# EvoProject_2_0.net
KiCad netlist of a schematic drawn in Altium Designer
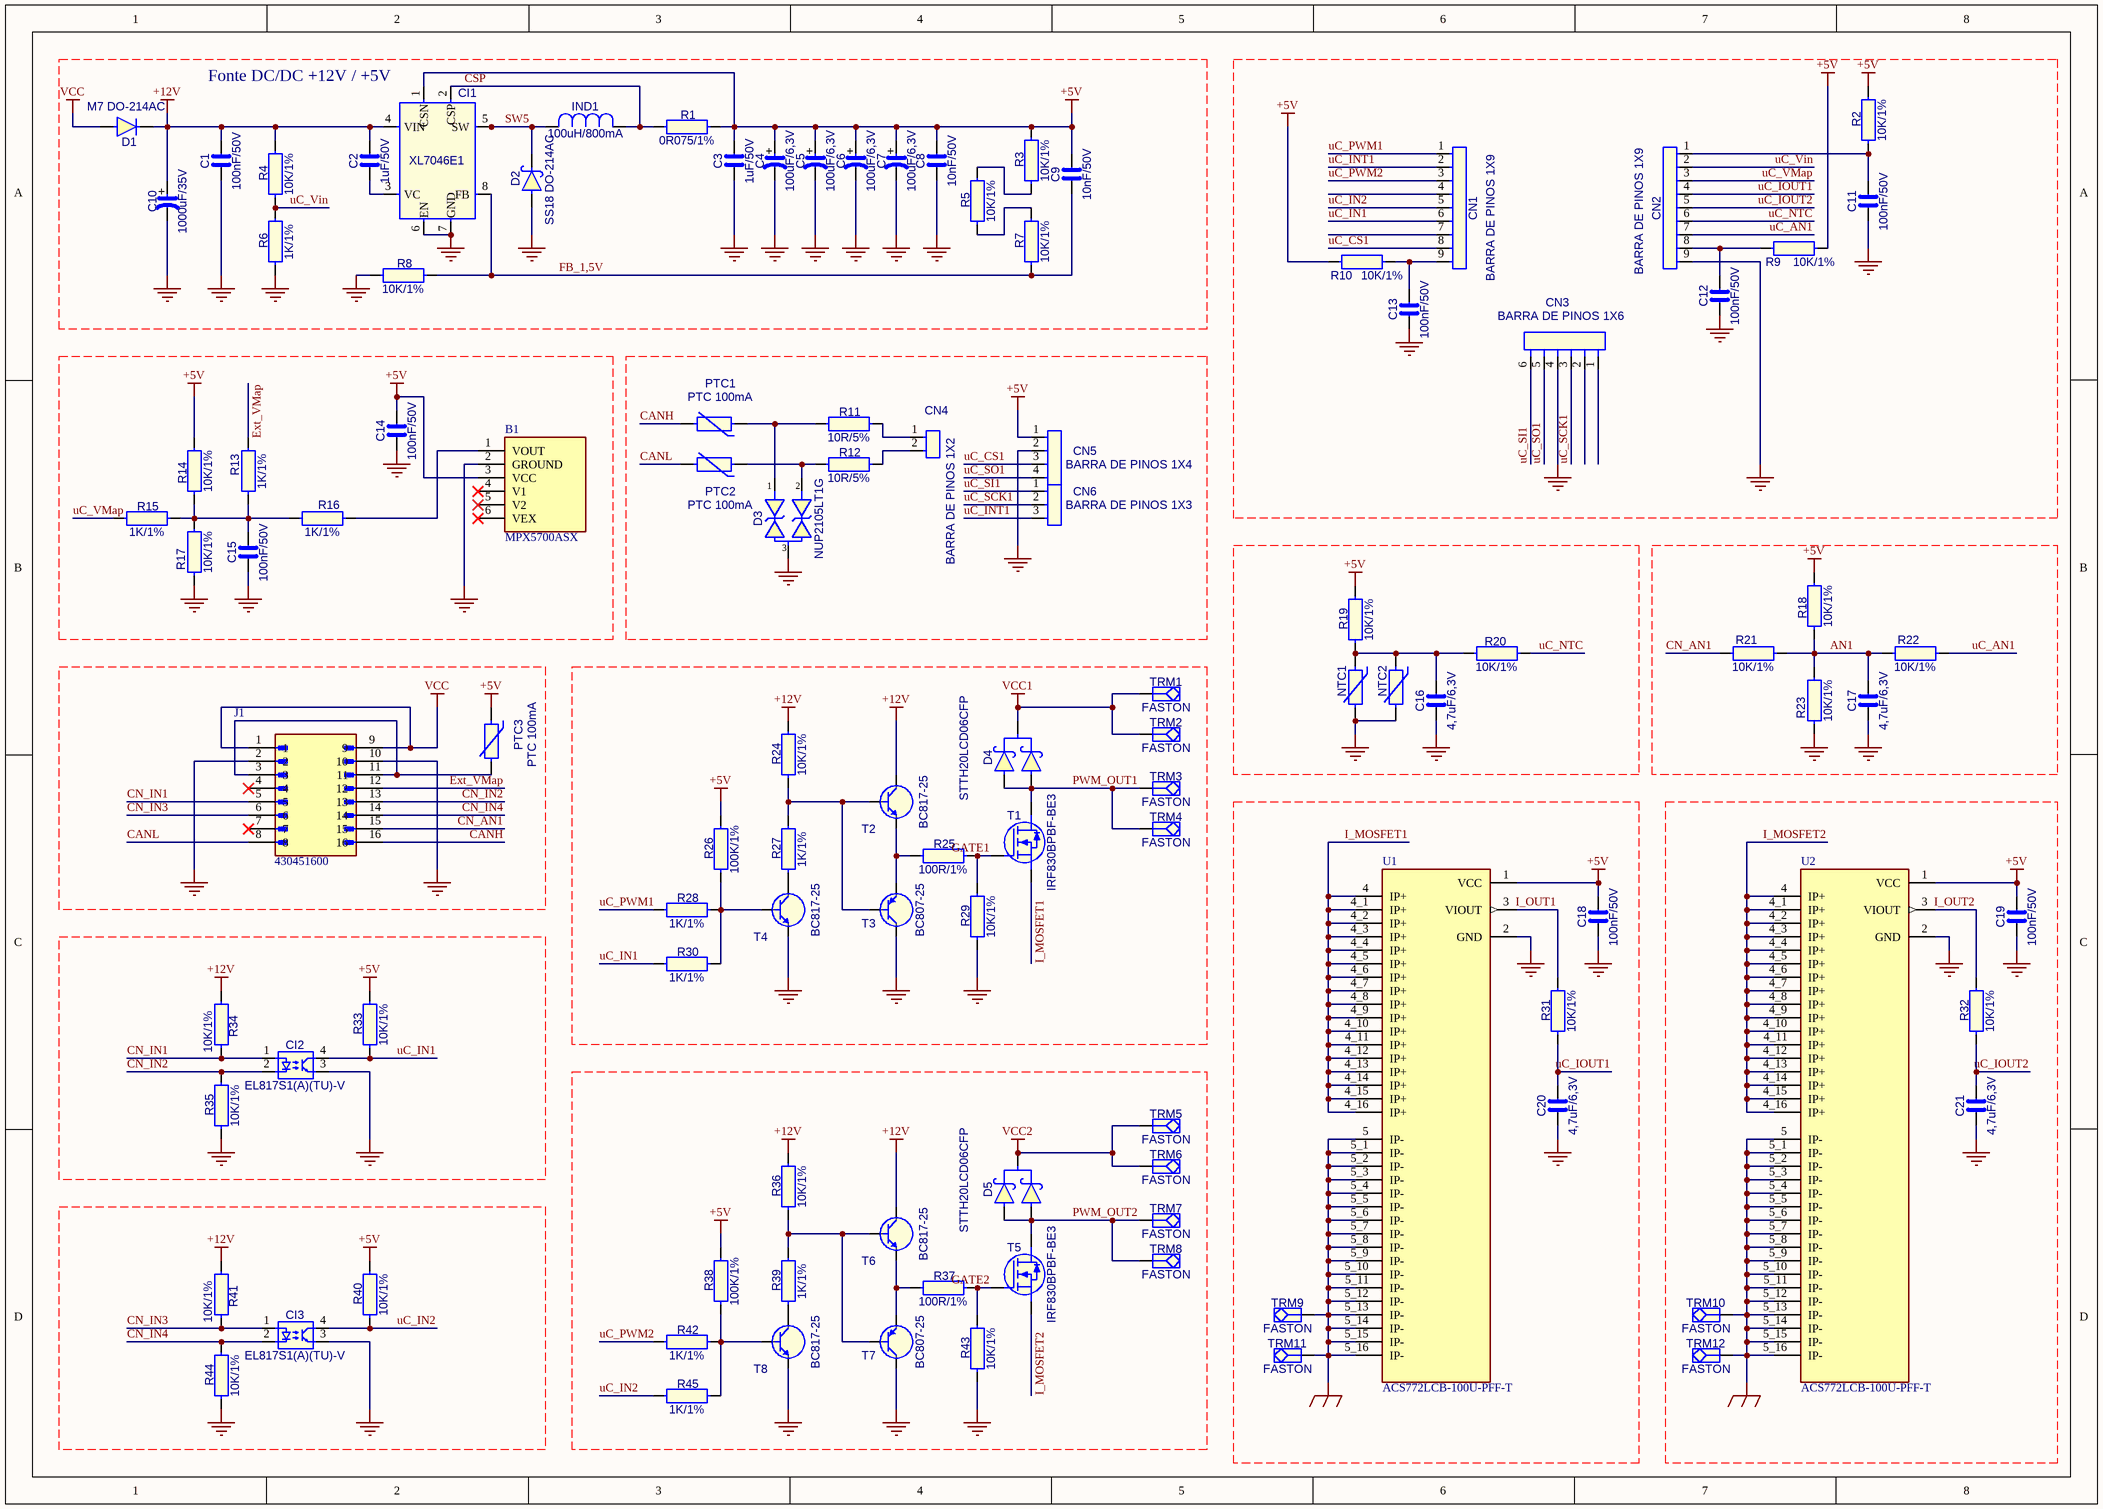
[diagram p0: EvoProject 2.0.SchDoc]

(export (version "E")
  (design (tool "Eeschema 10.0.6"))
  (components
    (comp (ref "B1")
      (value "MPX5700ASX")
      (footprint "MPX5700ASX")
      (libsource (lib "Inova_2015") (part "MPX5700ASX"))
    )
    (comp (ref "C1")
      (value "100nF/50V")
      (footprint "CAP SMD CE 0603 HR")
      (description "CAPACITOR SMD CE 0603 100nF 50V 10% X7R")
      (libsource (lib "INOVA SISTEMAS ELETRONICOS") (part "CAP_NP"))
    )
    (comp (ref "C2")
      (value "1uF/50V")
      (footprint "CAP SMD CE 0603 HR")
      (description "CAPACITOR SMD CE 0603 1uF 50V 10% X5R")
      (libsource (lib "INOVA SISTEMAS ELETRONICOS") (part "CAP_NP"))
    )
    (comp (ref "C3")
      (value "1uF/50V")
      (footprint "CAP SMD CE 0603 HR")
      (description "CAPACITOR SMD CE 0603 1uF 50V 10% X5R")
      (libsource (lib "INOVA SISTEMAS ELETRONICOS") (part "CAP_NP"))
    )
    (comp (ref "C4")
      (value "100uF/6,3V")
      (footprint "CAP SMD EL D.6,30 H.5,40 P.4,80 HR")
      (description "CAPACITOR SMD EL D.6.3 H.5.4mm 100uF 6.3V 20% BESR")
      (libsource (lib "INOVA SISTEMAS ELETRONICOS") (part "CAP_P"))
    )
    (comp (ref "C5")
      (value "100uF/6,3V")
      (footprint "CAP SMD EL D.6,30 H.5,40 P.4,80 HR")
      (description "CAPACITOR SMD EL D.6.3 H.5.4mm 100uF 6.3V 20% BESR")
      (libsource (lib "INOVA SISTEMAS ELETRONICOS") (part "CAP_P"))
    )
    (comp (ref "C6")
      (value "100uF/6,3V")
      (footprint "CAP SMD EL D.6,30 H.5,40 P.4,80 HR")
      (description "CAPACITOR SMD EL D.6.3 H.5.4mm 100uF 6.3V 20% BESR")
      (libsource (lib "INOVA SISTEMAS ELETRONICOS") (part "CAP_P"))
    )
    (comp (ref "C7")
      (value "100uF/6,3V")
      (footprint "CAP SMD EL D.6,30 H.5,40 P.4,80 HR")
      (description "CAPACITOR SMD EL D.6.3 H.5.4mm 100uF 6.3V 20% BESR")
      (libsource (lib "INOVA SISTEMAS ELETRONICOS") (part "CAP_P"))
    )
    (comp (ref "C8")
      (value "10nF/50V")
      (footprint "CAP SMD CE 0603 HR")
      (description "CAPACITOR SMD CE 0603 10nF 50V 20% X7R")
      (libsource (lib "INOVA SISTEMAS ELETRONICOS") (part "CAP_NP"))
    )
    (comp (ref "C9")
      (value "10nF/50V")
      (footprint "CAP SMD CE 0603 HR")
      (description "CAPACITOR SMD CE 0603 10nF 50V 20% X7R")
      (libsource (lib "INOVA SISTEMAS ELETRONICOS") (part "CAP_NP"))
    )
    (comp (ref "C10")
      (value "1000uF/35V")
      (footprint "CAP PTH EL D.13,00 H.20,00 P.5,00 RD MW")
      (description "CAPACITOR PTH EL 1000/35 20%")
      (libsource (lib "INOVA SISTEMAS ELETRONICOS") (part "CAP_P"))
    )
    (comp (ref "C11")
      (value "100nF/50V")
      (footprint "CAP SMD CE 0603 HR")
      (description "CAPACITOR SMD CE 0603 100nF 50V 10% X7R")
      (libsource (lib "INOVA SISTEMAS ELETRONICOS") (part "CAP_NP"))
    )
    (comp (ref "C12")
      (value "100nF/50V")
      (footprint "CAP SMD CE 0603 HR")
      (description "CAPACITOR SMD CE 0603 100nF 50V 10% X7R")
      (libsource (lib "INOVA SISTEMAS ELETRONICOS") (part "CAP_NP"))
    )
    (comp (ref "C13")
      (value "100nF/50V")
      (footprint "CAP SMD CE 0603 HR")
      (description "CAPACITOR SMD CE 0603 100nF 50V 10% X7R")
      (libsource (lib "INOVA SISTEMAS ELETRONICOS") (part "CAP_NP"))
    )
    (comp (ref "C14")
      (value "100nF/50V")
      (footprint "CAP SMD CE 0603 HR")
      (description "CAPACITOR SMD CE 0603 100nF 50V 10% X7R")
      (libsource (lib "INOVA SISTEMAS ELETRONICOS") (part "CAP_NP"))
    )
    (comp (ref "C15")
      (value "100nF/50V")
      (footprint "CAP SMD CE 0603 HR")
      (description "CAPACITOR SMD CE 0603 100nF 50V 10% X7R")
      (libsource (lib "INOVA SISTEMAS ELETRONICOS") (part "CAP_NP"))
    )
    (comp (ref "C16")
      (value "4,7uF/6,3V")
      (footprint "CAP SMD CE 0603 HR")
      (description "CAPACITOR SMD CE 0603 4,7uF 6.3V 10% X5R")
      (libsource (lib "INOVA SISTEMAS ELETRONICOS") (part "CAP_NP"))
    )
    (comp (ref "C17")
      (value "4,7uF/6,3V")
      (footprint "CAP SMD CE 0603 HR")
      (description "CAPACITOR SMD CE 0603 4,7uF 6.3V 10% X5R")
      (libsource (lib "INOVA SISTEMAS ELETRONICOS") (part "CAP_NP"))
    )
    (comp (ref "C18")
      (value "100nF/50V")
      (footprint "CAP SMD CE 0603 HR")
      (description "CAPACITOR SMD CE 0603 100nF 50V 10% X7R")
      (libsource (lib "INOVA SISTEMAS ELETRONICOS") (part "CAP_NP"))
    )
    (comp (ref "C19")
      (value "100nF/50V")
      (footprint "CAP SMD CE 0603 HR")
      (description "CAPACITOR SMD CE 0603 100nF 50V 10% X7R")
      (libsource (lib "INOVA SISTEMAS ELETRONICOS") (part "CAP_NP"))
    )
    (comp (ref "C20")
      (value "4,7uF/6,3V")
      (footprint "CAP SMD CE 0603 HR")
      (description "CAPACITOR SMD CE 0603 4,7uF 6.3V 10% X5R")
      (libsource (lib "INOVA SISTEMAS ELETRONICOS") (part "CAP_NP"))
    )
    (comp (ref "C21")
      (value "4,7uF/6,3V")
      (footprint "CAP SMD CE 0603 HR")
      (description "CAPACITOR SMD CE 0603 4,7uF 6.3V 10% X5R")
      (libsource (lib "INOVA SISTEMAS ELETRONICOS") (part "CAP_NP"))
    )
    (comp (ref "CI1")
      (value "XL7046E1")
      (footprint "GEN SMD SOIC8 TP P.1,27 MR")
      (description "CI SMD REBAIXADOR DE TENSÃO XL7046E1")
      (libsource (lib "INOVA SISTEMAS ELETRONICOS") (part "CI_XL7046"))
    )
    (comp (ref "CI2")
      (value "EL817S1(A)(TU)-V")
      (footprint "GEN SMD SOIC4 P.1,27 MR")
      (description "CI OPTOACOPLADOR SMD DIP-4 1CH 817 70V 80~160%")
      (libsource (lib "INOVA SISTEMAS ELETRONICOS") (part "OPT_4 pinos"))
    )
    (comp (ref "CI3")
      (value "EL817S1(A)(TU)-V")
      (footprint "GEN SMD SOIC4 P.1,27 MR")
      (description "CI OPTOACOPLADOR SMD DIP-4 1CH 817 70V 80~160%")
      (libsource (lib "INOVA SISTEMAS ELETRONICOS") (part "OPT_4 pinos"))
    )
    (comp (ref "CN1")
      (value "BARRA DE PINOS 1X9")
      (footprint "CON PTH BAR P.2,54 1x9 180D MW")
      (description "BARRA DE PINOS 180° RETOS (CORTAR 9 PINOS)")
      (libsource (lib "INOVA SISTEMAS ELETRONICOS") (part "CON_9 Vias Simples"))
    )
    (comp (ref "CN2")
      (value "BARRA DE PINOS 1X9")
      (footprint "CON PTH BAR P.2,54 1x9 180D MW")
      (description "BARRA DE PINOS 180° RETOS (CORTAR 9 PINOS)")
      (libsource (lib "") (part "CON_9 Vias Simples_1"))
    )
    (comp (ref "CN3")
      (value "BARRA DE PINOS 1X6")
      (footprint "CON PTH BAR  W. L. H. P.2,54mm 1x6 180D MW")
      (description "CONECTOR BARRA DE PINOS 180° 1X6")
      (libsource (lib "INOVA SISTEMAS ELETRONICOS") (part "CON_6 Vias Simples"))
    )
    (comp (ref "CN4")
      (value "BARRA DE PINOS 1X2")
      (footprint "CON PTH BAR  W. L. H. P.02,54mm 1x2 180D MW")
      (description "BARRA DE PINOS 180° RETOS (CORTAR 2 PINOS)")
      (libsource (lib "INOVA SISTEMAS ELETRONICOS") (part "CON_2 Vias Simples"))
    )
    (comp (ref "CN5")
      (value "BARRA DE PINOS 1X4")
      (footprint "CON PTH BAR  W. L. H. P.02,54mm 1x4 180D MW")
      (description "BARRA DE PINOS 180° RETOS (CORTAR 4 PINOS)")
      (libsource (lib "INOVA SISTEMAS ELETRONICOS") (part "CON_4 Vias Simples"))
    )
    (comp (ref "CN6")
      (value "BARRA DE PINOS 1X3")
      (footprint "CON PTH BAR  W. L. H. P.2,54mm 1x3 180D MW")
      (description "BARRA DE PINOS 180° RETOS (CORTAR 3 PINOS)")
      (libsource (lib "INOVA SISTEMAS ELETRONICOS") (part "CON_3 Vias Simples"))
    )
    (comp (ref "D1")
      (value "M7 DO-214AC")
      (footprint "DIO SMD SMA DO214AC MR")
      (description "DIODO SMD 1N4007 SMA")
      (libsource (lib "INOVA SISTEMAS ELETRONICOS") (part "DIO_Comum"))
    )
    (comp (ref "D2")
      (value "SS18 DO-214AC")
      (footprint "DIO SMD SMA DO214AC HR")
      (description "DIODO SMD SS18 1A 80V SCHOTTKY")
      (libsource (lib "INOVA SISTEMAS ELETRONICOS") (part "DIO_Schottky"))
    )
    (comp (ref "D3")
      (value "NUP2105LT1G")
      (footprint "GEN SMD SOT23-3 TO-236AA MR")
      (description "DIODO SMD TVS SOT23 24V 50A 350W")
      (libsource (lib "INOVA SISTEMAS ELETRONICOS") (part "DIO_NUP2105L"))
    )
    (comp (ref "D4")
      (value "STTH20LCD06CFP")
      (footprint "GEN PTH TO-220AB P.2,54 LW")
      (description "DIODO PTH STTH20LCD06CFP ULTRAFAST (PF07-6.5-V)")
      (libsource (lib "INOVA SISTEMAS ELETRONICOS") (part "DIO_Schottky Duplo"))
    )
    (comp (ref "D5")
      (value "STTH20LCD06CFP")
      (footprint "GEN PTH TO-220AB P.2,54 LW")
      (description "DIODO PTH STTH20LCD06CFP ULTRAFAST (PF07-6.5-V)")
      (libsource (lib "INOVA SISTEMAS ELETRONICOS") (part "DIO_Schottky Duplo"))
    )
    (comp (ref "IND1")
      (value "100uH/800mA")
      (footprint "IND SMD L.6,30 P.4,82 MR")
      (description "INDUTOR SMD 100uH 800mA")
      (libsource (lib "INOVA SISTEMAS ELETRONICOS") (part "IND_2 Terminais"))
    )
    (comp (ref "J1")
      (value "430451600")
      (footprint "MOLEX_430451600")
      (description "Conn Wire to Board HDR 16 POS 3mm Solder RA Side Entry Thru-Hole Micro-Fit 3.0â„¢ Tray")
      (fields (field (name "MF") "Molex"))
      (libsource (lib "430451600") (part "430451600"))
    )
    (comp (ref "NTC1")
      (value "MF52A103H3950(A2)")
      (footprint "RES PTH NTC RADIAL P.2,54 LW")
      (description "TERMISTOR NTC 10K (PF)")
      (libsource (lib "INOVA SISTEMAS ELETRONICOS") (part "RES_NTC"))
    )
    (comp (ref "NTC2")
      (value "NTC 10k")
      (footprint "RES SMD CH 0805 HR")
      (description "TERMISTOR SMD NTC 0805 10K BETA 3970 3%")
      (libsource (lib "INOVA SISTEMAS ELETRONICOS") (part "RES_NTC"))
    )
    (comp (ref "PTC1")
      (value "PTC 100mA")
      (footprint "PTC SMD CH 0805 HR")
      (description "TERMISTOR SMD PTC 0805 0,1A 24V NHC")
      (libsource (lib "INOVA SISTEMAS ELETRONICOS") (part "RES_PTC"))
    )
    (comp (ref "PTC2")
      (value "PTC 100mA")
      (footprint "PTC SMD CH 0805 HR")
      (description "TERMISTOR SMD PTC 0805 0,1A 24V NHC")
      (libsource (lib "INOVA SISTEMAS ELETRONICOS") (part "RES_PTC"))
    )
    (comp (ref "PTC3")
      (value "PTC 100mA")
      (footprint "PTC SMD CH 0805 HR")
      (description "TERMISTOR SMD PTC 0805 0,1A 24V NHC")
      (libsource (lib "") (part "RES_PTC_1"))
    )
    (comp (ref "R1")
      (value "0R075/1%")
      (footprint "RES SMD CH 1206 HR")
      (description "RESISTOR SMD CH 1206 0R075 1% 1/4W")
      (libsource (lib "") (part "RES_Geral_1"))
    )
    (comp (ref "R2")
      (value "10K/1%")
      (footprint "RES SMD CH 0603 HR")
      (description "RESISTOR SMD CH 0603 10K 1% 1/10W")
      (libsource (lib "INOVA SISTEMAS ELETRONICOS") (part "RES_Geral"))
    )
    (comp (ref "R3")
      (value "10K/1%")
      (footprint "RES SMD CH 0603 HR")
      (description "RESISTOR SMD CH 0603 10K 1% 1/10W")
      (libsource (lib "INOVA SISTEMAS ELETRONICOS") (part "RES_Geral"))
    )
    (comp (ref "R4")
      (value "10K/1%")
      (footprint "RES SMD CH 0603 HR")
      (description "RESISTOR SMD CH 0603 10K 1% 1/10W")
      (libsource (lib "INOVA SISTEMAS ELETRONICOS") (part "RES_Geral"))
    )
    (comp (ref "R5")
      (value "10K/1%")
      (footprint "RES SMD CH 0603 HR")
      (description "RESISTOR SMD CH 0603 10K 1% 1/10W")
      (libsource (lib "INOVA SISTEMAS ELETRONICOS") (part "RES_Geral"))
    )
    (comp (ref "R6")
      (value "1K/1%")
      (footprint "RES SMD CH 0603 HR")
      (description "RESISTOR SMD CH 0603 1K 1% 1/10W")
      (libsource (lib "INOVA SISTEMAS ELETRONICOS") (part "RES_Geral"))
    )
    (comp (ref "R7")
      (value "10K/1%")
      (footprint "RES SMD CH 0603 HR")
      (description "RESISTOR SMD CH 0603 10K 1% 1/10W")
      (libsource (lib "INOVA SISTEMAS ELETRONICOS") (part "RES_Geral"))
    )
    (comp (ref "R8")
      (value "10K/1%")
      (footprint "RES SMD CH 0603 HR")
      (description "RESISTOR SMD CH 0603 10K 1% 1/10W")
      (libsource (lib "") (part "RES_Geral_1"))
    )
    (comp (ref "R9")
      (value "10K/1%")
      (footprint "RES SMD CH 0603 HR")
      (description "RESISTOR SMD CH 0603 10K 1% 1/10W")
      (libsource (lib "") (part "RES_Geral_3"))
    )
    (comp (ref "R10")
      (value "10K/1%")
      (footprint "RES SMD CH 0603 HR")
      (description "RESISTOR SMD CH 0603 10K 1% 1/10W")
      (libsource (lib "") (part "RES_Geral_3"))
    )
    (comp (ref "R11")
      (value "10R/5%")
      (footprint "RES SMD CH 0603 HR")
      (description "RESISTOR SMD CH 0603 10R 5% 1/10W")
      (libsource (lib "") (part "RES_Geral_1"))
    )
    (comp (ref "R12")
      (value "10R/5%")
      (footprint "RES SMD CH 0603 HR")
      (description "RESISTOR SMD CH 0603 10R 5% 1/10W")
      (libsource (lib "") (part "RES_Geral_1"))
    )
    (comp (ref "R13")
      (value "1K/1%")
      (footprint "RES SMD CH 0603 HR")
      (description "RESISTOR SMD CH 0603 1K 1% 1/10W")
      (libsource (lib "INOVA SISTEMAS ELETRONICOS") (part "RES_Geral"))
    )
    (comp (ref "R14")
      (value "10K/1%")
      (footprint "RES SMD CH 0603 HR")
      (description "RESISTOR SMD CH 0603 10K 1% 1/10W")
      (libsource (lib "") (part "RES_Geral_2"))
    )
    (comp (ref "R15")
      (value "1K/1%")
      (footprint "RES SMD CH 0603 HR")
      (description "RESISTOR SMD CH 0603 1K 1% 1/10W")
      (libsource (lib "") (part "RES_Geral_1"))
    )
    (comp (ref "R16")
      (value "1K/1%")
      (footprint "RES SMD CH 0603 HR")
      (description "RESISTOR SMD CH 0603 1K 1% 1/10W")
      (libsource (lib "") (part "RES_Geral_1"))
    )
    (comp (ref "R17")
      (value "10K/1%")
      (footprint "RES SMD CH 0603 HR")
      (description "RESISTOR SMD CH 0603 10K 1% 1/10W")
      (libsource (lib "") (part "RES_Geral_2"))
    )
    (comp (ref "R18")
      (value "10K/1%")
      (footprint "RES SMD CH 0603 HR")
      (description "RESISTOR SMD CH 0603 10K 1% 1/10W")
      (libsource (lib "") (part "RES_Geral_2"))
    )
    (comp (ref "R19")
      (value "10K/1%")
      (footprint "RES SMD CH 0603 HR")
      (description "RESISTOR SMD CH 0603 10K 1% 1/10W")
      (libsource (lib "INOVA SISTEMAS ELETRONICOS") (part "RES_Geral"))
    )
    (comp (ref "R20")
      (value "10K/1%")
      (footprint "RES SMD CH 0603 HR")
      (description "RESISTOR SMD CH 0603 10K 1% 1/10W")
      (libsource (lib "") (part "RES_Geral_3"))
    )
    (comp (ref "R21")
      (value "10K/1%")
      (footprint "RES SMD CH 0603 HR")
      (description "RESISTOR SMD CH 0603 10K 1% 1/10W")
      (libsource (lib "") (part "RES_Geral_3"))
    )
    (comp (ref "R22")
      (value "10K/1%")
      (footprint "RES SMD CH 0603 HR")
      (description "RESISTOR SMD CH 0603 10K 1% 1/10W")
      (libsource (lib "") (part "RES_Geral_3"))
    )
    (comp (ref "R23")
      (value "10K/1%")
      (footprint "RES SMD CH 0603 HR")
      (description "RESISTOR SMD CH 0603 10K 1% 1/10W")
      (libsource (lib "") (part "RES_Geral_2"))
    )
    (comp (ref "R24")
      (value "10K/1%")
      (footprint "RES SMD CH 0603 HR")
      (description "RESISTOR SMD CH 0603 10K 1% 1/10W")
      (libsource (lib "INOVA SISTEMAS ELETRONICOS") (part "RES_Geral"))
    )
    (comp (ref "R25")
      (value "100R/1%")
      (footprint "RES SMD CH 0603 HR")
      (description "RESISTOR SMD CH 0603 100R 1% 1/10W")
      (libsource (lib "") (part "RES_Geral_1"))
    )
    (comp (ref "R26")
      (value "100K/1%")
      (footprint "RES SMD CH 0603 HR")
      (description "RESISTOR SMD CH 0603 100K 1% 1/10W")
      (libsource (lib "INOVA SISTEMAS ELETRONICOS") (part "RES_Geral"))
    )
    (comp (ref "R27")
      (value "1K/1%")
      (footprint "RES SMD CH 0603 HR")
      (description "RESISTOR SMD CH 0603 1K 1% 1/10W")
      (libsource (lib "INOVA SISTEMAS ELETRONICOS") (part "RES_Geral"))
    )
    (comp (ref "R28")
      (value "1K/1%")
      (footprint "RES SMD CH 0603 HR")
      (description "RESISTOR SMD CH 0603 1K 1% 1/10W")
      (libsource (lib "") (part "RES_Geral_1"))
    )
    (comp (ref "R29")
      (value "10K/1%")
      (footprint "RES SMD CH 0603 HR")
      (description "RESISTOR SMD CH 0603 10K 1% 1/10W")
      (libsource (lib "INOVA SISTEMAS ELETRONICOS") (part "RES_Geral"))
    )
    (comp (ref "R30")
      (value "1K/1%")
      (footprint "RES SMD CH 0603 HR")
      (description "RESISTOR SMD CH 0603 1K 1% 1/10W")
      (libsource (lib "") (part "RES_Geral_1"))
    )
    (comp (ref "R31")
      (value "10K/1%")
      (footprint "RES SMD CH 0603 HR")
      (description "RESISTOR SMD CH 0603 10K 1% 1/10W")
      (libsource (lib "INOVA SISTEMAS ELETRONICOS") (part "RES_Geral"))
    )
    (comp (ref "R32")
      (value "10K/1%")
      (footprint "RES SMD CH 0603 HR")
      (description "RESISTOR SMD CH 0603 10K 1% 1/10W")
      (libsource (lib "INOVA SISTEMAS ELETRONICOS") (part "RES_Geral"))
    )
    (comp (ref "R33")
      (value "10K/1%")
      (footprint "RES SMD CH 0603 HR")
      (description "RESISTOR SMD CH 0603 10K 1% 1/10W")
      (libsource (lib "INOVA SISTEMAS ELETRONICOS") (part "RES_Geral"))
    )
    (comp (ref "R34")
      (value "10K/1%")
      (footprint "RES SMD CH 0603 HR")
      (description "RESISTOR SMD CH 0603 10K 1% 1/10W")
      (libsource (lib "") (part "RES_Geral_3"))
    )
    (comp (ref "R35")
      (value "10K/1%")
      (footprint "RES SMD CH 0603 HR")
      (description "RESISTOR SMD CH 0603 10K 1% 1/10W")
      (libsource (lib "INOVA SISTEMAS ELETRONICOS") (part "RES_Geral"))
    )
    (comp (ref "R36")
      (value "10K/1%")
      (footprint "RES SMD CH 0603 HR")
      (description "RESISTOR SMD CH 0603 10K 1% 1/10W")
      (libsource (lib "INOVA SISTEMAS ELETRONICOS") (part "RES_Geral"))
    )
    (comp (ref "R37")
      (value "100R/1%")
      (footprint "RES SMD CH 0603 HR")
      (description "RESISTOR SMD CH 0603 100R 1% 1/10W")
      (libsource (lib "") (part "RES_Geral_1"))
    )
    (comp (ref "R38")
      (value "100K/1%")
      (footprint "RES SMD CH 0603 HR")
      (description "RESISTOR SMD CH 0603 100K 1% 1/10W")
      (libsource (lib "INOVA SISTEMAS ELETRONICOS") (part "RES_Geral"))
    )
    (comp (ref "R39")
      (value "1K/1%")
      (footprint "RES SMD CH 0603 HR")
      (description "RESISTOR SMD CH 0603 1K 1% 1/10W")
      (libsource (lib "INOVA SISTEMAS ELETRONICOS") (part "RES_Geral"))
    )
    (comp (ref "R40")
      (value "10K/1%")
      (footprint "RES SMD CH 0603 HR")
      (description "RESISTOR SMD CH 0603 10K 1% 1/10W")
      (libsource (lib "INOVA SISTEMAS ELETRONICOS") (part "RES_Geral"))
    )
    (comp (ref "R41")
      (value "10K/1%")
      (footprint "RES SMD CH 0603 HR")
      (description "RESISTOR SMD CH 0603 10K 1% 1/10W")
      (libsource (lib "") (part "RES_Geral_3"))
    )
    (comp (ref "R42")
      (value "1K/1%")
      (footprint "RES SMD CH 0603 HR")
      (description "RESISTOR SMD CH 0603 1K 1% 1/10W")
      (libsource (lib "") (part "RES_Geral_1"))
    )
    (comp (ref "R43")
      (value "10K/1%")
      (footprint "RES SMD CH 0603 HR")
      (description "RESISTOR SMD CH 0603 10K 1% 1/10W")
      (libsource (lib "INOVA SISTEMAS ELETRONICOS") (part "RES_Geral"))
    )
    (comp (ref "R44")
      (value "10K/1%")
      (footprint "RES SMD CH 0603 HR")
      (description "RESISTOR SMD CH 0603 10K 1% 1/10W")
      (libsource (lib "INOVA SISTEMAS ELETRONICOS") (part "RES_Geral"))
    )
    (comp (ref "R45")
      (value "1K/1%")
      (footprint "RES SMD CH 0603 HR")
      (description "RESISTOR SMD CH 0603 1K 1% 1/10W")
      (libsource (lib "") (part "RES_Geral_1"))
    )
    (comp (ref "T1")
      (value "IRF830BPBF-BE3")
      (footprint "GEN PTH TO-220AB P.2,54 LW")
      (description "TRANSISTOR PTH MOSFET IRF830BPBF-BE3 500V, 5,5A @ 25C°")
      (libsource (lib "INOVA SISTEMAS ELETRONICOS") (part "TRA_MOSFET_N-DPAK TO-252-3 TO-220AB"))
    )
    (comp (ref "T2")
      (value "BC817-25")
      (footprint "GEN SMD SOT23-3 TO-236AA MR")
      (description "TRANSISTOR SMD 817/25")
      (libsource (lib "INOVA SISTEMAS ELETRONICOS") (part "TRA_NPN SOT-23-3L"))
    )
    (comp (ref "T3")
      (value "BC807-25")
      (footprint "GEN SMD SOT23-3 TO-236AA MR")
      (description "TRANSISTOR SMD 807/25")
      (libsource (lib "INOVA SISTEMAS ELETRONICOS") (part "TRA_PNP SOT-23-3L"))
    )
    (comp (ref "T4")
      (value "BC817-25")
      (footprint "GEN SMD SOT23-3 TO-236AA MR")
      (description "TRANSISTOR SMD 817/25")
      (libsource (lib "INOVA SISTEMAS ELETRONICOS") (part "TRA_NPN SOT-23-3L"))
    )
    (comp (ref "T5")
      (value "IRF830BPBF-BE3")
      (footprint "GEN PTH TO-220AB P.2,54 LW")
      (description "TRANSISTOR PTH MOSFET IRF830BPBF-BE3 500V, 5,5A @ 25C°")
      (libsource (lib "INOVA SISTEMAS ELETRONICOS") (part "TRA_MOSFET_N-DPAK TO-252-3 TO-220AB"))
    )
    (comp (ref "T6")
      (value "BC817-25")
      (footprint "GEN SMD SOT23-3 TO-236AA MR")
      (description "TRANSISTOR SMD 817/25")
      (libsource (lib "INOVA SISTEMAS ELETRONICOS") (part "TRA_NPN SOT-23-3L"))
    )
    (comp (ref "T7")
      (value "BC807-25")
      (footprint "GEN SMD SOT23-3 TO-236AA MR")
      (description "TRANSISTOR SMD 807/25")
      (libsource (lib "INOVA SISTEMAS ELETRONICOS") (part "TRA_PNP SOT-23-3L"))
    )
    (comp (ref "T8")
      (value "BC817-25")
      (footprint "GEN SMD SOT23-3 TO-236AA MR")
      (description "TRANSISTOR SMD 817/25")
      (libsource (lib "INOVA SISTEMAS ELETRONICOS") (part "TRA_NPN SOT-23-3L"))
    )
    (comp (ref "TRM1")
      (value "FASTON")
      (footprint "Terminal Faston Macho 180° OBLONGO COM SUPORTE")
      (description "TERMINAL P/ PCI 180° 6,35mmX14,2mm BAIONETA")
      (libsource (lib "") (part "CON_TERMINAL_1"))
    )
    (comp (ref "TRM2")
      (value "FASTON")
      (footprint "Terminal Faston Macho 180° OBLONGO COM SUPORTE")
      (description "TERMINAL P/ PCI 180° 6,35mmX14,2mm BAIONETA")
      (libsource (lib "") (part "CON_TERMINAL_1"))
    )
    (comp (ref "TRM3")
      (value "FASTON")
      (footprint "Terminal Faston Macho 180° OBLONGO COM SUPORTE")
      (description "TERMINAL P/ PCI 180° 6,35mmX14,2mm BAIONETA")
      (libsource (lib "") (part "CON_TERMINAL_1"))
    )
    (comp (ref "TRM4")
      (value "FASTON")
      (footprint "Terminal Faston Macho 180° OBLONGO COM SUPORTE")
      (description "TERMINAL P/ PCI 180° 6,35mmX14,2mm BAIONETA")
      (libsource (lib "") (part "CON_TERMINAL_1"))
    )
    (comp (ref "TRM5")
      (value "FASTON")
      (footprint "Terminal Faston Macho 180° OBLONGO COM SUPORTE")
      (description "TERMINAL P/ PCI 180° 6,35mmX14,2mm BAIONETA")
      (libsource (lib "") (part "CON_TERMINAL_1"))
    )
    (comp (ref "TRM6")
      (value "FASTON")
      (footprint "Terminal Faston Macho 180° OBLONGO COM SUPORTE")
      (description "TERMINAL P/ PCI 180° 6,35mmX14,2mm BAIONETA")
      (libsource (lib "") (part "CON_TERMINAL_1"))
    )
    (comp (ref "TRM7")
      (value "FASTON")
      (footprint "Terminal Faston Macho 180° OBLONGO COM SUPORTE")
      (description "TERMINAL P/ PCI 180° 6,35mmX14,2mm BAIONETA")
      (libsource (lib "") (part "CON_TERMINAL_1"))
    )
    (comp (ref "TRM8")
      (value "FASTON")
      (footprint "Terminal Faston Macho 180° OBLONGO COM SUPORTE")
      (description "TERMINAL P/ PCI 180° 6,35mmX14,2mm BAIONETA")
      (libsource (lib "") (part "CON_TERMINAL_1"))
    )
    (comp (ref "TRM9")
      (value "FASTON")
      (footprint "Terminal Faston Macho 180° OBLONGO COM SUPORTE")
      (description "TERMINAL P/ PCI 180° 6,35mmX14,2mm BAIONETA")
      (libsource (lib "INOVA SISTEMAS ELETRONICOS") (part "CON_TERMINAL"))
    )
    (comp (ref "TRM10")
      (value "FASTON")
      (footprint "Terminal Faston Macho 180° OBLONGO COM SUPORTE")
      (description "TERMINAL P/ PCI 180° 6,35mmX14,2mm BAIONETA")
      (libsource (lib "INOVA SISTEMAS ELETRONICOS") (part "CON_TERMINAL"))
    )
    (comp (ref "TRM11")
      (value "FASTON")
      (footprint "Terminal Faston Macho 180° OBLONGO COM SUPORTE")
      (description "TERMINAL P/ PCI 180° 6,35mmX14,2mm BAIONETA")
      (libsource (lib "INOVA SISTEMAS ELETRONICOS") (part "CON_TERMINAL"))
    )
    (comp (ref "TRM12")
      (value "FASTON")
      (footprint "Terminal Faston Macho 180° OBLONGO COM SUPORTE")
      (description "TERMINAL P/ PCI 180° 6,35mmX14,2mm BAIONETA")
      (libsource (lib "INOVA SISTEMAS ELETRONICOS") (part "CON_TERMINAL"))
    )
    (comp (ref "U1")
      (value "ACS772LCB-100U-PFF-T")
      (footprint "XDCR_ACS772LCB-100U-PFF-T")
      (description "Current Sensor 100A 1 Channel Hall Effect Unidirectional 5-CB Formed Leads, PFF")
      (fields (field (name "MF") "Allegro MicroSystems LLC"))
      (libsource (lib "ACS772LCB-100U-PFF-T") (part "ACS772LCB-100U-PFF-T"))
    )
    (comp (ref "U2")
      (value "ACS772LCB-100U-PFF-T")
      (footprint "XDCR_ACS772LCB-100U-PFF-T")
      (description "Current Sensor 100A 1 Channel Hall Effect Unidirectional 5-CB Formed Leads, PFF")
      (fields (field (name "MF") "Allegro MicroSystems LLC"))
      (libsource (lib "ACS772LCB-100U-PFF-T") (part "ACS772LCB-100U-PFF-T"))
    )
  )
  (nets
    (net (code "1") (name "+5V") (class "Default")
      (node (ref "B1") (pin "3") (pinfunction "VCC_3") (pintype "passive"))
      (node (ref "C14") (pin "1") (pinfunction "1_1") (pintype "passive"))
      (node (ref "C18") (pin "1") (pinfunction "1_1") (pintype "passive"))
      (node (ref "C19") (pin "1") (pinfunction "1_1") (pintype "passive"))
      (node (ref "C3") (pin "1") (pinfunction "1_1") (pintype "passive"))
      (node (ref "C4") (pin "2") (pinfunction "Plus_2") (pintype "passive"))
      (node (ref "C5") (pin "2") (pinfunction "Plus_2") (pintype "passive"))
      (node (ref "C6") (pin "2") (pinfunction "Plus_2") (pintype "passive"))
      (node (ref "C7") (pin "2") (pinfunction "Plus_2") (pintype "passive"))
      (node (ref "C8") (pin "1") (pinfunction "1_1") (pintype "passive"))
      (node (ref "C9") (pin "1") (pinfunction "1_1") (pintype "passive"))
      (node (ref "CI1") (pin "1") (pinfunction "CSN_1") (pintype "passive"))
      (node (ref "CN5") (pin "1") (pinfunction "1_1") (pintype "passive"))
      (node (ref "PTC3") (pin "2") (pinfunction "2_2") (pintype "passive"))
      (node (ref "R1") (pin "2") (pinfunction "2_2") (pintype "passive"))
      (node (ref "R10") (pin "2") (pinfunction "2_2") (pintype "passive"))
      (node (ref "R14") (pin "1") (pinfunction "1_1") (pintype "passive"))
      (node (ref "R18") (pin "1") (pinfunction "1_1") (pintype "passive"))
      (node (ref "R19") (pin "2") (pinfunction "2_2") (pintype "passive"))
      (node (ref "R2") (pin "2") (pinfunction "2_2") (pintype "passive"))
      (node (ref "R26") (pin "2") (pinfunction "2_2") (pintype "passive"))
      (node (ref "R3") (pin "2") (pinfunction "2_2") (pintype "passive"))
      (node (ref "R33") (pin "2") (pinfunction "2_2") (pintype "passive"))
      (node (ref "R38") (pin "2") (pinfunction "2_2") (pintype "passive"))
      (node (ref "R40") (pin "2") (pinfunction "2_2") (pintype "passive"))
      (node (ref "R9") (pin "1") (pinfunction "1_1") (pintype "passive"))
      (node (ref "U1") (pin "1") (pinfunction "VCC_1") (pintype "power_in"))
      (node (ref "U2") (pin "1") (pinfunction "VCC_1") (pintype "power_in"))
    )
    (net (code "2") (name "+12V") (class "Default")
      (node (ref "C1") (pin "1") (pinfunction "1_1") (pintype "passive"))
      (node (ref "C10") (pin "2") (pinfunction "Plus_2") (pintype "passive"))
      (node (ref "C2") (pin "1") (pinfunction "1_1") (pintype "passive"))
      (node (ref "CI1") (pin "4") (pinfunction "VIN_4") (pintype "power_in"))
      (node (ref "D1") (pin "1") (pinfunction "K_1") (pintype "passive"))
      (node (ref "R24") (pin "2") (pinfunction "2_2") (pintype "passive"))
      (node (ref "R34") (pin "1") (pinfunction "1_1") (pintype "passive"))
      (node (ref "R36") (pin "2") (pinfunction "2_2") (pintype "passive"))
      (node (ref "R4") (pin "2") (pinfunction "2_2") (pintype "passive"))
      (node (ref "R41") (pin "1") (pinfunction "1_1") (pintype "passive"))
      (node (ref "T2") (pin "3") (pinfunction "C_3") (pintype "passive"))
      (node (ref "T6") (pin "3") (pinfunction "C_3") (pintype "passive"))
    )
    (net (code "3") (name "/AN1") (class "Default")
      (node (ref "C17") (pin "1") (pinfunction "1_1") (pintype "passive"))
      (node (ref "R18") (pin "2") (pinfunction "2_2") (pintype "passive"))
      (node (ref "R21") (pin "1") (pinfunction "1_1") (pintype "passive"))
      (node (ref "R22") (pin "2") (pinfunction "2_2") (pintype "passive"))
      (node (ref "R23") (pin "1") (pinfunction "1_1") (pintype "passive"))
    )
    (net (code "4") (name "/CANH") (class "Default")
      (node (ref "J1") (pin "16") (pinfunction "16_16") (pintype "passive"))
      (node (ref "PTC1") (pin "1") (pinfunction "1_1") (pintype "passive"))
    )
    (net (code "5") (name "/CANL") (class "Default")
      (node (ref "J1") (pin "8") (pinfunction "8_8") (pintype "passive"))
      (node (ref "PTC2") (pin "1") (pinfunction "1_1") (pintype "passive"))
    )
    (net (code "6") (name "/CN_AN1") (class "Default")
      (node (ref "J1") (pin "15") (pinfunction "15_15") (pintype "passive"))
      (node (ref "R21") (pin "2") (pinfunction "2_2") (pintype "passive"))
    )
    (net (code "7") (name "/CN_IN1") (class "Default")
      (node (ref "CI2") (pin "1") (pinfunction "A_1") (pintype "passive"))
      (node (ref "J1") (pin "5") (pinfunction "5_5") (pintype "passive"))
      (node (ref "R34") (pin "2") (pinfunction "2_2") (pintype "passive"))
    )
    (net (code "8") (name "/CN_IN2") (class "Default")
      (node (ref "CI2") (pin "2") (pinfunction "K_2") (pintype "passive"))
      (node (ref "J1") (pin "13") (pinfunction "13_13") (pintype "passive"))
      (node (ref "R35") (pin "2") (pinfunction "2_2") (pintype "passive"))
    )
    (net (code "9") (name "/CN_IN3") (class "Default")
      (node (ref "CI3") (pin "1") (pinfunction "A_1") (pintype "passive"))
      (node (ref "J1") (pin "6") (pinfunction "6_6") (pintype "passive"))
      (node (ref "R41") (pin "2") (pinfunction "2_2") (pintype "passive"))
    )
    (net (code "10") (name "/CN_IN4") (class "Default")
      (node (ref "CI3") (pin "2") (pinfunction "K_2") (pintype "passive"))
      (node (ref "J1") (pin "14") (pinfunction "14_14") (pintype "passive"))
      (node (ref "R44") (pin "2") (pinfunction "2_2") (pintype "passive"))
    )
    (net (code "11") (name "/CSP") (class "Default")
      (node (ref "CI1") (pin "2") (pinfunction "CSP_2") (pintype "passive"))
      (node (ref "IND1") (pin "2") (pinfunction "2_2") (pintype "passive"))
      (node (ref "R1") (pin "1") (pinfunction "1_1") (pintype "passive"))
    )
    (net (code "12") (name "/Ext_VMap") (class "Default")
      (node (ref "J1") (pin "12") (pinfunction "12_12") (pintype "passive"))
      (node (ref "R13") (pin "2") (pinfunction "2_2") (pintype "passive"))
    )
    (net (code "13") (name "/FB_1,5V") (class "Default")
      (node (ref "C9") (pin "2") (pinfunction "2_2") (pintype "passive"))
      (node (ref "CI1") (pin "8") (pinfunction "FB_8") (pintype "passive"))
      (node (ref "R7") (pin "1") (pinfunction "1_1") (pintype "passive"))
      (node (ref "R8") (pin "2") (pinfunction "2_2") (pintype "passive"))
    )
    (net (code "14") (name "/GATE1") (class "Default")
      (node (ref "R25") (pin "2") (pinfunction "2_2") (pintype "passive"))
      (node (ref "R29") (pin "2") (pinfunction "2_2") (pintype "passive"))
      (node (ref "T1") (pin "1") (pinfunction "G_1") (pintype "passive"))
    )
    (net (code "15") (name "/GATE2") (class "Default")
      (node (ref "R37") (pin "2") (pinfunction "2_2") (pintype "passive"))
      (node (ref "R43") (pin "2") (pinfunction "2_2") (pintype "passive"))
      (node (ref "T5") (pin "1") (pinfunction "G_1") (pintype "passive"))
    )
    (net (code "16") (name "/I_MOSFET1") (class "Default")
      (node (ref "T1") (pin "3") (pinfunction "S_3") (pintype "passive"))
      (node (ref "U1") (pin "4") (pinfunction "IP+_4") (pintype "passive"))
      (node (ref "U1") (pin "4_1") (pinfunction "IP+_4_1") (pintype "passive"))
      (node (ref "U1") (pin "4_10") (pinfunction "IP+_4_10") (pintype "passive"))
      (node (ref "U1") (pin "4_11") (pinfunction "IP+_4_11") (pintype "passive"))
      (node (ref "U1") (pin "4_12") (pinfunction "IP+_4_12") (pintype "passive"))
      (node (ref "U1") (pin "4_13") (pinfunction "IP+_4_13") (pintype "passive"))
      (node (ref "U1") (pin "4_14") (pinfunction "IP+_4_14") (pintype "passive"))
      (node (ref "U1") (pin "4_15") (pinfunction "IP+_4_15") (pintype "passive"))
      (node (ref "U1") (pin "4_16") (pinfunction "IP+_4_16") (pintype "passive"))
      (node (ref "U1") (pin "4_2") (pinfunction "IP+_4_2") (pintype "passive"))
      (node (ref "U1") (pin "4_3") (pinfunction "IP+_4_3") (pintype "passive"))
      (node (ref "U1") (pin "4_4") (pinfunction "IP+_4_4") (pintype "passive"))
      (node (ref "U1") (pin "4_5") (pinfunction "IP+_4_5") (pintype "passive"))
      (node (ref "U1") (pin "4_6") (pinfunction "IP+_4_6") (pintype "passive"))
      (node (ref "U1") (pin "4_7") (pinfunction "IP+_4_7") (pintype "passive"))
      (node (ref "U1") (pin "4_8") (pinfunction "IP+_4_8") (pintype "passive"))
      (node (ref "U1") (pin "4_9") (pinfunction "IP+_4_9") (pintype "passive"))
    )
    (net (code "17") (name "/I_MOSFET2") (class "Default")
      (node (ref "T5") (pin "3") (pinfunction "S_3") (pintype "passive"))
      (node (ref "U2") (pin "4") (pinfunction "IP+_4") (pintype "passive"))
      (node (ref "U2") (pin "4_1") (pinfunction "IP+_4_1") (pintype "passive"))
      (node (ref "U2") (pin "4_10") (pinfunction "IP+_4_10") (pintype "passive"))
      (node (ref "U2") (pin "4_11") (pinfunction "IP+_4_11") (pintype "passive"))
      (node (ref "U2") (pin "4_12") (pinfunction "IP+_4_12") (pintype "passive"))
      (node (ref "U2") (pin "4_13") (pinfunction "IP+_4_13") (pintype "passive"))
      (node (ref "U2") (pin "4_14") (pinfunction "IP+_4_14") (pintype "passive"))
      (node (ref "U2") (pin "4_15") (pinfunction "IP+_4_15") (pintype "passive"))
      (node (ref "U2") (pin "4_16") (pinfunction "IP+_4_16") (pintype "passive"))
      (node (ref "U2") (pin "4_2") (pinfunction "IP+_4_2") (pintype "passive"))
      (node (ref "U2") (pin "4_3") (pinfunction "IP+_4_3") (pintype "passive"))
      (node (ref "U2") (pin "4_4") (pinfunction "IP+_4_4") (pintype "passive"))
      (node (ref "U2") (pin "4_5") (pinfunction "IP+_4_5") (pintype "passive"))
      (node (ref "U2") (pin "4_6") (pinfunction "IP+_4_6") (pintype "passive"))
      (node (ref "U2") (pin "4_7") (pinfunction "IP+_4_7") (pintype "passive"))
      (node (ref "U2") (pin "4_8") (pinfunction "IP+_4_8") (pintype "passive"))
      (node (ref "U2") (pin "4_9") (pinfunction "IP+_4_9") (pintype "passive"))
    )
    (net (code "18") (name "/I_OUT1") (class "Default")
      (node (ref "R31") (pin "2") (pinfunction "2_2") (pintype "passive"))
      (node (ref "U1") (pin "3") (pinfunction "VIOUT_3") (pintype "output"))
    )
    (net (code "19") (name "/I_OUT2") (class "Default")
      (node (ref "R32") (pin "2") (pinfunction "2_2") (pintype "passive"))
      (node (ref "U2") (pin "3") (pinfunction "VIOUT_3") (pintype "output"))
    )
    (net (code "20") (name "/PWM_OUT1") (class "Default")
      (node (ref "D4") (pin "1") (pinfunction "A1_1") (pintype "passive"))
      (node (ref "D4") (pin "3") (pinfunction "A2_3") (pintype "passive"))
      (node (ref "T1") (pin "2") (pinfunction "D_2") (pintype "passive"))
      (node (ref "TRM3") (pin "1") (pinfunction "1_1") (pintype "passive"))
      (node (ref "TRM4") (pin "1") (pinfunction "1_1") (pintype "passive"))
    )
    (net (code "21") (name "/PWM_OUT2") (class "Default")
      (node (ref "D5") (pin "1") (pinfunction "A1_1") (pintype "passive"))
      (node (ref "D5") (pin "3") (pinfunction "A2_3") (pintype "passive"))
      (node (ref "T5") (pin "2") (pinfunction "D_2") (pintype "passive"))
      (node (ref "TRM7") (pin "1") (pinfunction "1_1") (pintype "passive"))
      (node (ref "TRM8") (pin "1") (pinfunction "1_1") (pintype "passive"))
    )
    (net (code "22") (name "/SW5") (class "Default")
      (node (ref "CI1") (pin "5") (pinfunction "SW_5") (pintype "passive"))
      (node (ref "CI1") (pin "9") (pinfunction "TAB_9") (pintype "passive"))
      (node (ref "D2") (pin "1") (pinfunction "K_1") (pintype "passive"))
      (node (ref "IND1") (pin "1") (pinfunction "1_1") (pintype "passive"))
    )
    (net (code "23") (name "/uC_AN1") (class "Default")
      (node (ref "CN2") (pin "7") (pinfunction "7_7") (pintype "passive"))
      (node (ref "R22") (pin "1") (pinfunction "1_1") (pintype "passive"))
    )
    (net (code "24") (name "/uC_CS1") (class "Default")
      (node (ref "CN1") (pin "8") (pinfunction "8_8") (pintype "passive"))
      (node (ref "CN5") (pin "3") (pinfunction "3_3") (pintype "passive"))
    )
    (net (code "25") (name "/uC_IN1") (class "Default")
      (node (ref "CI2") (pin "4") (pinfunction "C_4") (pintype "passive"))
      (node (ref "CN1") (pin "6") (pinfunction "6_6") (pintype "passive"))
      (node (ref "R30") (pin "1") (pinfunction "1_1") (pintype "passive"))
      (node (ref "R33") (pin "1") (pinfunction "1_1") (pintype "passive"))
    )
    (net (code "26") (name "/uC_IN2") (class "Default")
      (node (ref "CI3") (pin "4") (pinfunction "C_4") (pintype "passive"))
      (node (ref "CN1") (pin "5") (pinfunction "5_5") (pintype "passive"))
      (node (ref "R40") (pin "1") (pinfunction "1_1") (pintype "passive"))
      (node (ref "R45") (pin "1") (pinfunction "1_1") (pintype "passive"))
    )
    (net (code "27") (name "/uC_INT1") (class "Default")
      (node (ref "CN1") (pin "2") (pinfunction "2_2") (pintype "passive"))
      (node (ref "CN6") (pin "3") (pinfunction "3_3") (pintype "passive"))
    )
    (net (code "28") (name "/uC_IOUT1") (class "Default")
      (node (ref "C20") (pin "1") (pinfunction "1_1") (pintype "passive"))
      (node (ref "CN2") (pin "4") (pinfunction "4_4") (pintype "passive"))
      (node (ref "R31") (pin "1") (pinfunction "1_1") (pintype "passive"))
    )
    (net (code "29") (name "/uC_IOUT2") (class "Default")
      (node (ref "C21") (pin "1") (pinfunction "1_1") (pintype "passive"))
      (node (ref "CN2") (pin "5") (pinfunction "5_5") (pintype "passive"))
      (node (ref "R32") (pin "1") (pinfunction "1_1") (pintype "passive"))
    )
    (net (code "30") (name "/uC_NTC") (class "Default")
      (node (ref "CN2") (pin "6") (pinfunction "6_6") (pintype "passive"))
      (node (ref "R20") (pin "1") (pinfunction "1_1") (pintype "passive"))
    )
    (net (code "31") (name "/uC_PWM1") (class "Default")
      (node (ref "CN1") (pin "1") (pinfunction "1_1") (pintype "passive"))
      (node (ref "R28") (pin "1") (pinfunction "1_1") (pintype "passive"))
    )
    (net (code "32") (name "/uC_PWM2") (class "Default")
      (node (ref "CN1") (pin "3") (pinfunction "3_3") (pintype "passive"))
      (node (ref "R42") (pin "1") (pinfunction "1_1") (pintype "passive"))
    )
    (net (code "33") (name "/uC_SCK1") (class "Default")
      (node (ref "CN3") (pin "3") (pinfunction "3_3") (pintype "passive"))
      (node (ref "CN6") (pin "2") (pinfunction "2_2") (pintype "passive"))
    )
    (net (code "34") (name "/uC_SI1") (class "Default")
      (node (ref "CN3") (pin "6") (pinfunction "6_6") (pintype "passive"))
      (node (ref "CN6") (pin "1") (pinfunction "1_1") (pintype "passive"))
    )
    (net (code "35") (name "/uC_SO1") (class "Default")
      (node (ref "CN3") (pin "5") (pinfunction "5_5") (pintype "passive"))
      (node (ref "CN5") (pin "4") (pinfunction "4_4") (pintype "passive"))
    )
    (net (code "36") (name "/uC_VMap") (class "Default")
      (node (ref "CN2") (pin "3") (pinfunction "3_3") (pintype "passive"))
      (node (ref "R15") (pin "1") (pinfunction "1_1") (pintype "passive"))
    )
    (net (code "37") (name "/uC_Vin") (class "Default")
      (node (ref "CN2") (pin "2") (pinfunction "2_2") (pintype "passive"))
      (node (ref "R4") (pin "1") (pinfunction "1_1") (pintype "passive"))
      (node (ref "R6") (pin "2") (pinfunction "2_2") (pintype "passive"))
    )
    (net (code "38") (name "GND") (class "Default")
      (node (ref "B1") (pin "2") (pinfunction "GROUND_2") (pintype "passive"))
      (node (ref "C1") (pin "2") (pinfunction "2_2") (pintype "passive"))
      (node (ref "C10") (pin "1") (pinfunction "Minus_1") (pintype "passive"))
      (node (ref "C11") (pin "2") (pinfunction "2_2") (pintype "passive"))
      (node (ref "C12") (pin "1") (pinfunction "1_1") (pintype "passive"))
      (node (ref "C13") (pin "1") (pinfunction "1_1") (pintype "passive"))
      (node (ref "C14") (pin "2") (pinfunction "2_2") (pintype "passive"))
      (node (ref "C15") (pin "2") (pinfunction "2_2") (pintype "passive"))
      (node (ref "C16") (pin "2") (pinfunction "2_2") (pintype "passive"))
      (node (ref "C17") (pin "2") (pinfunction "2_2") (pintype "passive"))
      (node (ref "C18") (pin "2") (pinfunction "2_2") (pintype "passive"))
      (node (ref "C19") (pin "2") (pinfunction "2_2") (pintype "passive"))
      (node (ref "C20") (pin "2") (pinfunction "2_2") (pintype "passive"))
      (node (ref "C21") (pin "2") (pinfunction "2_2") (pintype "passive"))
      (node (ref "C3") (pin "2") (pinfunction "2_2") (pintype "passive"))
      (node (ref "C4") (pin "1") (pinfunction "Minus_1") (pintype "passive"))
      (node (ref "C5") (pin "1") (pinfunction "Minus_1") (pintype "passive"))
      (node (ref "C6") (pin "1") (pinfunction "Minus_1") (pintype "passive"))
      (node (ref "C7") (pin "1") (pinfunction "Minus_1") (pintype "passive"))
      (node (ref "C8") (pin "2") (pinfunction "2_2") (pintype "passive"))
      (node (ref "CI1") (pin "6") (pinfunction "EN_6") (pintype "passive"))
      (node (ref "CI1") (pin "7") (pinfunction "GND_7") (pintype "passive"))
      (node (ref "CI2") (pin "3") (pinfunction "E_3") (pintype "passive"))
      (node (ref "CI3") (pin "3") (pinfunction "E_3") (pintype "passive"))
      (node (ref "CN2") (pin "9") (pinfunction "9_9") (pintype "passive"))
      (node (ref "CN3") (pin "4") (pinfunction "4_4") (pintype "passive"))
      (node (ref "CN5") (pin "2") (pinfunction "2_2") (pintype "passive"))
      (node (ref "D2") (pin "2") (pinfunction "A_2") (pintype "passive"))
      (node (ref "D3") (pin "3") (pinfunction "3_3") (pintype "passive"))
      (node (ref "J1") (pin "10") (pinfunction "10_10") (pintype "passive"))
      (node (ref "J1") (pin "2") (pinfunction "2_2") (pintype "passive"))
      (node (ref "NTC1") (pin "1") (pinfunction "1_1") (pintype "passive"))
      (node (ref "NTC2") (pin "1") (pinfunction "1_1") (pintype "passive"))
      (node (ref "R17") (pin "2") (pinfunction "2_2") (pintype "passive"))
      (node (ref "R23") (pin "2") (pinfunction "2_2") (pintype "passive"))
      (node (ref "R29") (pin "1") (pinfunction "1_1") (pintype "passive"))
      (node (ref "R35") (pin "1") (pinfunction "1_1") (pintype "passive"))
      (node (ref "R43") (pin "1") (pinfunction "1_1") (pintype "passive"))
      (node (ref "R44") (pin "1") (pinfunction "1_1") (pintype "passive"))
      (node (ref "R6") (pin "1") (pinfunction "1_1") (pintype "passive"))
      (node (ref "R8") (pin "1") (pinfunction "1_1") (pintype "passive"))
      (node (ref "T3") (pin "3") (pinfunction "C_3") (pintype "passive"))
      (node (ref "T4") (pin "2") (pinfunction "E_2") (pintype "passive"))
      (node (ref "T7") (pin "3") (pinfunction "C_3") (pintype "passive"))
      (node (ref "T8") (pin "2") (pinfunction "E_2") (pintype "passive"))
      (node (ref "U1") (pin "2") (pinfunction "GND_2") (pintype "power_in"))
      (node (ref "U2") (pin "2") (pinfunction "GND_2") (pintype "power_in"))
    )
    (net (code "39") (name "Net-(B1-VOUT)") (class "Default")
      (node (ref "B1") (pin "1") (pinfunction "VOUT_1") (pintype "passive"))
      (node (ref "R16") (pin "2") (pinfunction "2_2") (pintype "passive"))
    )
    (net (code "40") (name "Net-(C11-Pad1)") (class "Default")
      (node (ref "C11") (pin "1") (pinfunction "1_1") (pintype "passive"))
      (node (ref "CN2") (pin "1") (pinfunction "1_1") (pintype "passive"))
      (node (ref "R2") (pin "1") (pinfunction "1_1") (pintype "passive"))
    )
    (net (code "41") (name "Net-(C12-Pad2)") (class "Default")
      (node (ref "C12") (pin "2") (pinfunction "2_2") (pintype "passive"))
      (node (ref "CN2") (pin "8") (pinfunction "8_8") (pintype "passive"))
      (node (ref "R9") (pin "2") (pinfunction "2_2") (pintype "passive"))
    )
    (net (code "42") (name "Net-(C13-Pad2)") (class "Default")
      (node (ref "C13") (pin "2") (pinfunction "2_2") (pintype "passive"))
      (node (ref "CN1") (pin "9") (pinfunction "9_9") (pintype "passive"))
      (node (ref "R10") (pin "1") (pinfunction "1_1") (pintype "passive"))
    )
    (net (code "43") (name "Net-(C15-Pad1)") (class "Default")
      (node (ref "C15") (pin "1") (pinfunction "1_1") (pintype "passive"))
      (node (ref "R13") (pin "1") (pinfunction "1_1") (pintype "passive"))
      (node (ref "R14") (pin "2") (pinfunction "2_2") (pintype "passive"))
      (node (ref "R15") (pin "2") (pinfunction "2_2") (pintype "passive"))
      (node (ref "R16") (pin "1") (pinfunction "1_1") (pintype "passive"))
      (node (ref "R17") (pin "1") (pinfunction "1_1") (pintype "passive"))
    )
    (net (code "44") (name "Net-(C16-Pad1)") (class "Default")
      (node (ref "C16") (pin "1") (pinfunction "1_1") (pintype "passive"))
      (node (ref "NTC1") (pin "2") (pinfunction "2_2") (pintype "passive"))
      (node (ref "NTC2") (pin "2") (pinfunction "2_2") (pintype "passive"))
      (node (ref "R19") (pin "1") (pinfunction "1_1") (pintype "passive"))
      (node (ref "R20") (pin "2") (pinfunction "2_2") (pintype "passive"))
    )
    (net (code "45") (name "Net-(CI1-VC)") (class "Default")
      (node (ref "C2") (pin "2") (pinfunction "2_2") (pintype "passive"))
      (node (ref "CI1") (pin "3") (pinfunction "VC_3") (pintype "passive"))
    )
    (net (code "46") (name "Net-(CN4-Pad1)") (class "Default")
      (node (ref "CN4") (pin "1") (pinfunction "1_1") (pintype "passive"))
      (node (ref "R11") (pin "2") (pinfunction "2_2") (pintype "passive"))
    )
    (net (code "47") (name "Net-(CN4-Pad2)") (class "Default")
      (node (ref "CN4") (pin "2") (pinfunction "2_2") (pintype "passive"))
      (node (ref "R12") (pin "2") (pinfunction "2_2") (pintype "passive"))
    )
    (net (code "48") (name "Net-(D3-Pad1)") (class "Default")
      (node (ref "D3") (pin "1") (pinfunction "1_1") (pintype "passive"))
      (node (ref "PTC1") (pin "2") (pinfunction "2_2") (pintype "passive"))
      (node (ref "R11") (pin "1") (pinfunction "1_1") (pintype "passive"))
    )
    (net (code "49") (name "Net-(D3-Pad2)") (class "Default")
      (node (ref "D3") (pin "2") (pinfunction "2_2") (pintype "passive"))
      (node (ref "PTC2") (pin "2") (pinfunction "2_2") (pintype "passive"))
      (node (ref "R12") (pin "1") (pinfunction "1_1") (pintype "passive"))
    )
    (net (code "50") (name "Net-(J1-Pad11)") (class "Default")
      (node (ref "J1") (pin "11") (pinfunction "11_11") (pintype "passive"))
      (node (ref "J1") (pin "3") (pinfunction "3_3") (pintype "passive"))
      (node (ref "PTC3") (pin "1") (pinfunction "1_1") (pintype "passive"))
    )
    (net (code "51") (name "Net-(R3-Pad1)") (class "Default")
      (node (ref "R3") (pin "1") (pinfunction "1_1") (pintype "passive"))
      (node (ref "R5") (pin "2") (pinfunction "2_2") (pintype "passive"))
    )
    (net (code "52") (name "Net-(R5-Pad1)") (class "Default")
      (node (ref "R5") (pin "1") (pinfunction "1_1") (pintype "passive"))
      (node (ref "R7") (pin "2") (pinfunction "2_2") (pintype "passive"))
    )
    (net (code "53") (name "Net-(T2-B)") (class "Default")
      (node (ref "R24") (pin "1") (pinfunction "1_1") (pintype "passive"))
      (node (ref "R27") (pin "2") (pinfunction "2_2") (pintype "passive"))
      (node (ref "T2") (pin "1") (pinfunction "B_1") (pintype "passive"))
      (node (ref "T3") (pin "1") (pinfunction "B_1") (pintype "passive"))
    )
    (net (code "54") (name "Net-(T2-E)") (class "Default")
      (node (ref "R25") (pin "1") (pinfunction "1_1") (pintype "passive"))
      (node (ref "T2") (pin "2") (pinfunction "E_2") (pintype "passive"))
      (node (ref "T3") (pin "2") (pinfunction "E_2") (pintype "passive"))
    )
    (net (code "55") (name "Net-(T4-B)") (class "Default")
      (node (ref "R26") (pin "1") (pinfunction "1_1") (pintype "passive"))
      (node (ref "R28") (pin "2") (pinfunction "2_2") (pintype "passive"))
      (node (ref "R30") (pin "2") (pinfunction "2_2") (pintype "passive"))
      (node (ref "T4") (pin "1") (pinfunction "B_1") (pintype "passive"))
    )
    (net (code "56") (name "Net-(T4-C)") (class "Default")
      (node (ref "R27") (pin "1") (pinfunction "1_1") (pintype "passive"))
      (node (ref "T4") (pin "3") (pinfunction "C_3") (pintype "passive"))
    )
    (net (code "57") (name "Net-(T6-B)") (class "Default")
      (node (ref "R36") (pin "1") (pinfunction "1_1") (pintype "passive"))
      (node (ref "R39") (pin "2") (pinfunction "2_2") (pintype "passive"))
      (node (ref "T6") (pin "1") (pinfunction "B_1") (pintype "passive"))
      (node (ref "T7") (pin "1") (pinfunction "B_1") (pintype "passive"))
    )
    (net (code "58") (name "Net-(T6-E)") (class "Default")
      (node (ref "R37") (pin "1") (pinfunction "1_1") (pintype "passive"))
      (node (ref "T6") (pin "2") (pinfunction "E_2") (pintype "passive"))
      (node (ref "T7") (pin "2") (pinfunction "E_2") (pintype "passive"))
    )
    (net (code "59") (name "Net-(T8-B)") (class "Default")
      (node (ref "R38") (pin "1") (pinfunction "1_1") (pintype "passive"))
      (node (ref "R42") (pin "2") (pinfunction "2_2") (pintype "passive"))
      (node (ref "R45") (pin "2") (pinfunction "2_2") (pintype "passive"))
      (node (ref "T8") (pin "1") (pinfunction "B_1") (pintype "passive"))
    )
    (net (code "60") (name "Net-(T8-C)") (class "Default")
      (node (ref "R39") (pin "1") (pinfunction "1_1") (pintype "passive"))
      (node (ref "T8") (pin "3") (pinfunction "C_3") (pintype "passive"))
    )
    (net (code "61") (name "VCC") (class "Default")
      (node (ref "D1") (pin "2") (pinfunction "A_2") (pintype "passive"))
      (node (ref "J1") (pin "1") (pinfunction "1_1") (pintype "passive"))
      (node (ref "J1") (pin "9") (pinfunction "9_9") (pintype "passive"))
    )
    (net (code "62") (name "VCC1") (class "Default")
      (node (ref "D4") (pin "2") (pinfunction "K_2") (pintype "passive"))
      (node (ref "TRM1") (pin "1") (pinfunction "1_1") (pintype "passive"))
      (node (ref "TRM2") (pin "1") (pinfunction "1_1") (pintype "passive"))
    )
    (net (code "63") (name "VCC2") (class "Default")
      (node (ref "D5") (pin "2") (pinfunction "K_2") (pintype "passive"))
      (node (ref "TRM5") (pin "1") (pinfunction "1_1") (pintype "passive"))
      (node (ref "TRM6") (pin "1") (pinfunction "1_1") (pintype "passive"))
    )
    (net (code "64") (name "power_GND1") (class "Default")
      (node (ref "TRM11") (pin "1") (pinfunction "1_1") (pintype "passive"))
      (node (ref "TRM9") (pin "1") (pinfunction "1_1") (pintype "passive"))
      (node (ref "U1") (pin "5") (pinfunction "IP-_5") (pintype "passive"))
      (node (ref "U1") (pin "5_1") (pinfunction "IP-_5_1") (pintype "passive"))
      (node (ref "U1") (pin "5_10") (pinfunction "IP-_5_10") (pintype "passive"))
      (node (ref "U1") (pin "5_11") (pinfunction "IP-_5_11") (pintype "passive"))
      (node (ref "U1") (pin "5_12") (pinfunction "IP-_5_12") (pintype "passive"))
      (node (ref "U1") (pin "5_13") (pinfunction "IP-_5_13") (pintype "passive"))
      (node (ref "U1") (pin "5_14") (pinfunction "IP-_5_14") (pintype "passive"))
      (node (ref "U1") (pin "5_15") (pinfunction "IP-_5_15") (pintype "passive"))
      (node (ref "U1") (pin "5_16") (pinfunction "IP-_5_16") (pintype "passive"))
      (node (ref "U1") (pin "5_2") (pinfunction "IP-_5_2") (pintype "passive"))
      (node (ref "U1") (pin "5_3") (pinfunction "IP-_5_3") (pintype "passive"))
      (node (ref "U1") (pin "5_4") (pinfunction "IP-_5_4") (pintype "passive"))
      (node (ref "U1") (pin "5_5") (pinfunction "IP-_5_5") (pintype "passive"))
      (node (ref "U1") (pin "5_6") (pinfunction "IP-_5_6") (pintype "passive"))
      (node (ref "U1") (pin "5_7") (pinfunction "IP-_5_7") (pintype "passive"))
      (node (ref "U1") (pin "5_8") (pinfunction "IP-_5_8") (pintype "passive"))
      (node (ref "U1") (pin "5_9") (pinfunction "IP-_5_9") (pintype "passive"))
    )
    (net (code "65") (name "power_GND2") (class "Default")
      (node (ref "TRM10") (pin "1") (pinfunction "1_1") (pintype "passive"))
      (node (ref "TRM12") (pin "1") (pinfunction "1_1") (pintype "passive"))
      (node (ref "U2") (pin "5") (pinfunction "IP-_5") (pintype "passive"))
      (node (ref "U2") (pin "5_1") (pinfunction "IP-_5_1") (pintype "passive"))
      (node (ref "U2") (pin "5_10") (pinfunction "IP-_5_10") (pintype "passive"))
      (node (ref "U2") (pin "5_11") (pinfunction "IP-_5_11") (pintype "passive"))
      (node (ref "U2") (pin "5_12") (pinfunction "IP-_5_12") (pintype "passive"))
      (node (ref "U2") (pin "5_13") (pinfunction "IP-_5_13") (pintype "passive"))
      (node (ref "U2") (pin "5_14") (pinfunction "IP-_5_14") (pintype "passive"))
      (node (ref "U2") (pin "5_15") (pinfunction "IP-_5_15") (pintype "passive"))
      (node (ref "U2") (pin "5_16") (pinfunction "IP-_5_16") (pintype "passive"))
      (node (ref "U2") (pin "5_2") (pinfunction "IP-_5_2") (pintype "passive"))
      (node (ref "U2") (pin "5_3") (pinfunction "IP-_5_3") (pintype "passive"))
      (node (ref "U2") (pin "5_4") (pinfunction "IP-_5_4") (pintype "passive"))
      (node (ref "U2") (pin "5_5") (pinfunction "IP-_5_5") (pintype "passive"))
      (node (ref "U2") (pin "5_6") (pinfunction "IP-_5_6") (pintype "passive"))
      (node (ref "U2") (pin "5_7") (pinfunction "IP-_5_7") (pintype "passive"))
      (node (ref "U2") (pin "5_8") (pinfunction "IP-_5_8") (pintype "passive"))
      (node (ref "U2") (pin "5_9") (pinfunction "IP-_5_9") (pintype "passive"))
    )
    (net (code "66") (name "unconnected-(B1-V1-Pad4)") (class "Default")
      (node (ref "B1") (pin "4") (pinfunction "V1_4") (pintype "passive+no_connect"))
    )
    (net (code "67") (name "unconnected-(B1-V2-Pad5)") (class "Default")
      (node (ref "B1") (pin "5") (pinfunction "V2_5") (pintype "passive+no_connect"))
    )
    (net (code "68") (name "unconnected-(B1-VEX-Pad6)") (class "Default")
      (node (ref "B1") (pin "6") (pinfunction "VEX_6") (pintype "passive+no_connect"))
    )
    (net (code "69") (name "unconnected-(CN1-Pad4)") (class "Default")
      (node (ref "CN1") (pin "4") (pinfunction "4_4") (pintype "passive"))
    )
    (net (code "70") (name "unconnected-(CN1-Pad7)") (class "Default")
      (node (ref "CN1") (pin "7") (pinfunction "7_7") (pintype "passive"))
    )
    (net (code "71") (name "unconnected-(CN3-Pad1)") (class "Default")
      (node (ref "CN3") (pin "1") (pinfunction "1_1") (pintype "passive"))
    )
    (net (code "72") (name "unconnected-(CN3-Pad2)") (class "Default")
      (node (ref "CN3") (pin "2") (pinfunction "2_2") (pintype "passive"))
    )
    (net (code "73") (name "unconnected-(J1-Pad4)") (class "Default")
      (node (ref "J1") (pin "4") (pinfunction "4_4") (pintype "passive+no_connect"))
    )
    (net (code "74") (name "unconnected-(J1-Pad7)") (class "Default")
      (node (ref "J1") (pin "7") (pinfunction "7_7") (pintype "passive+no_connect"))
    )
  )
)
